# DeskAssistant_v19_v5.net
KiCad netlist of a schematic drawn in EAGLE
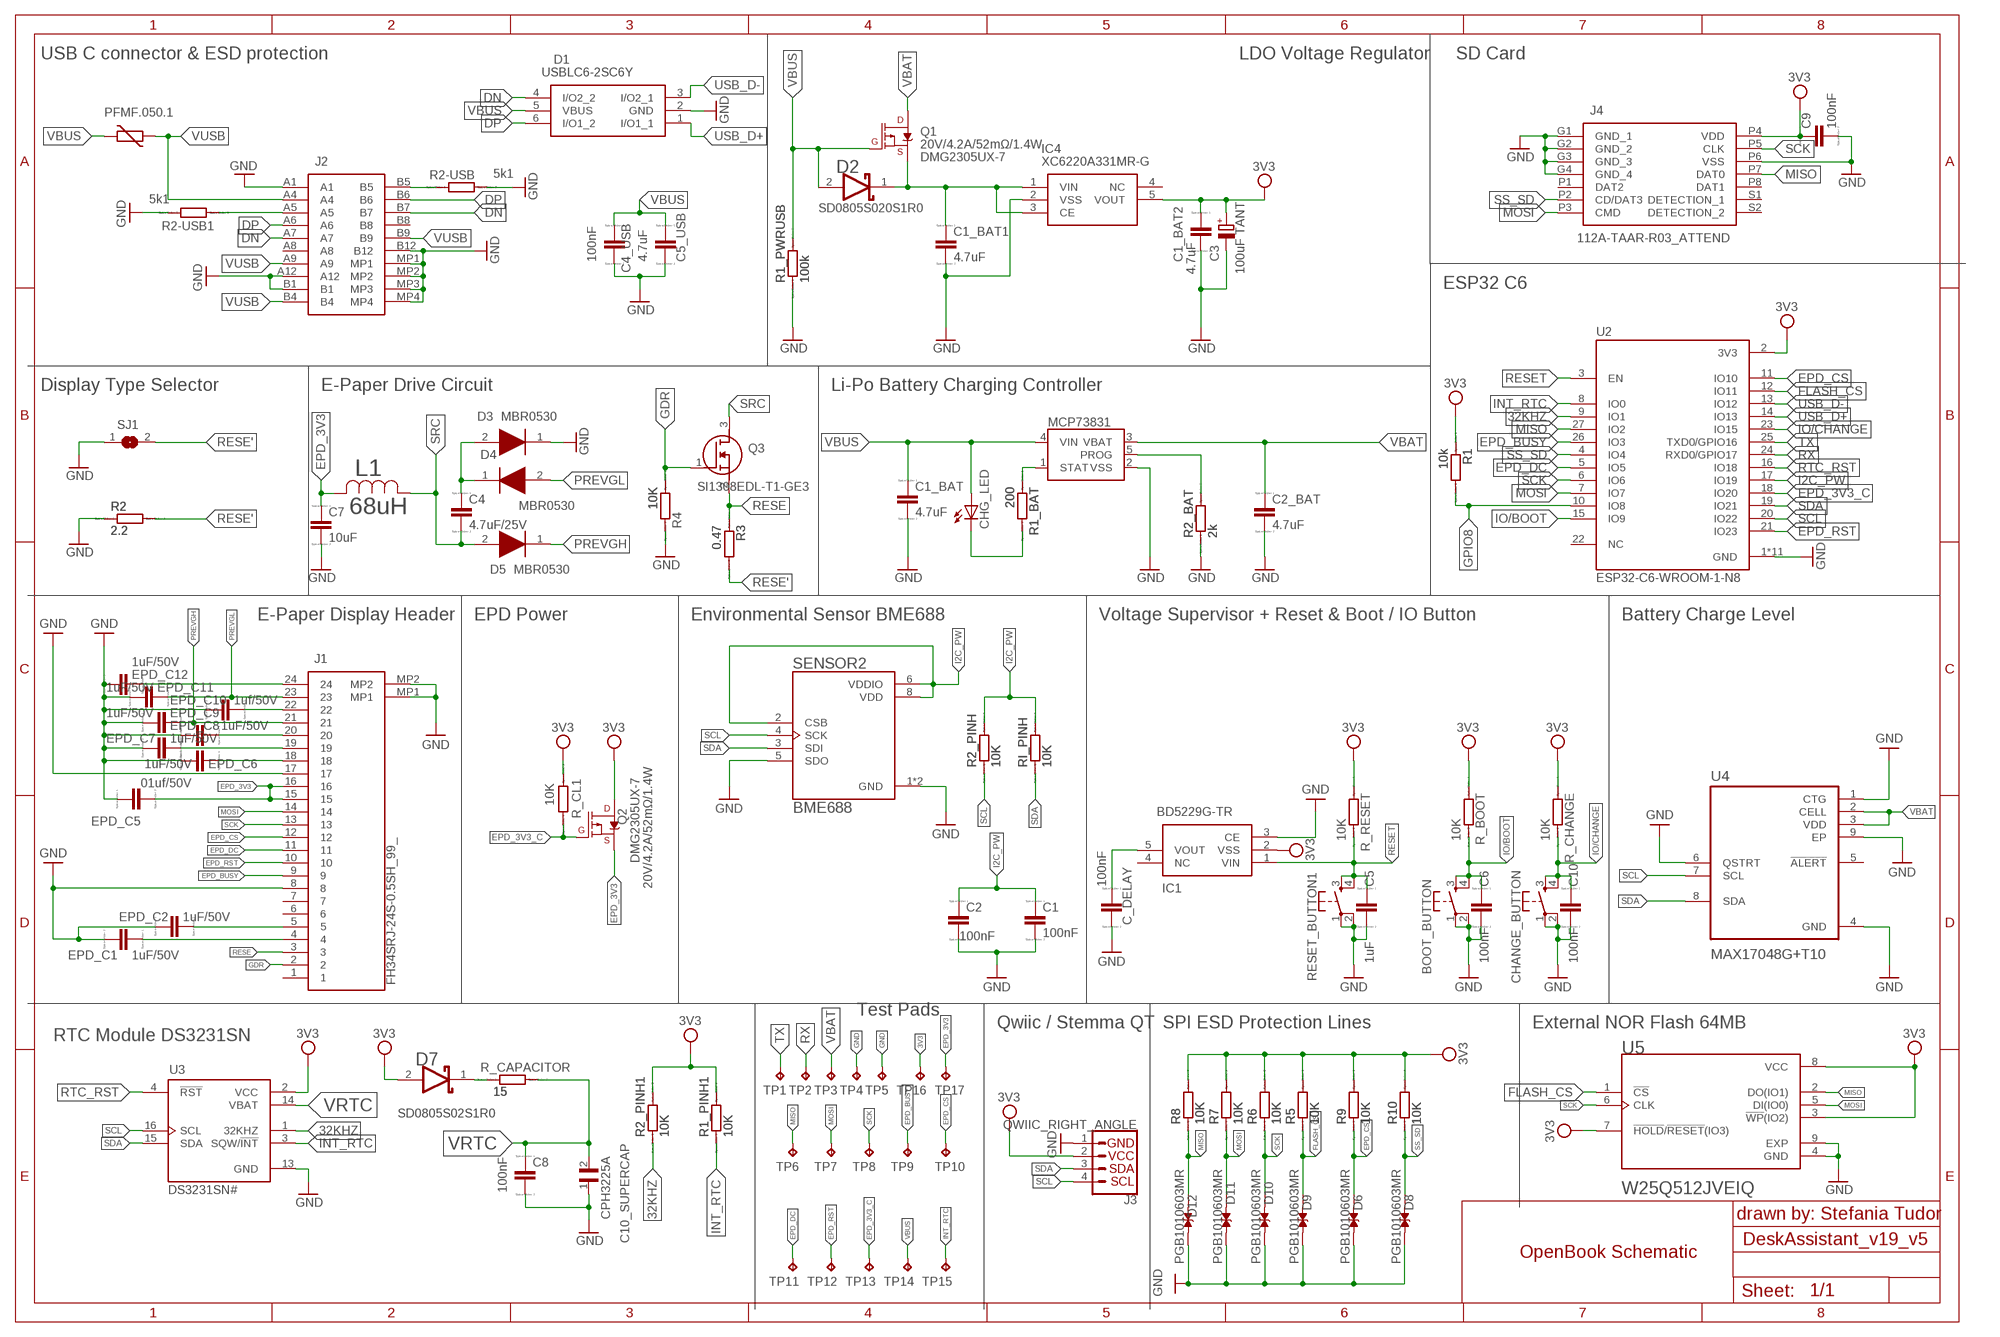
[diagram p0: schematic, sheet 1]

(export (version "E")
  (design (tool "Eeschema 10.0.6"))
  (components
    (comp (ref "BOOT_BUTTON")
      (value "BUTTON_CUSYOMV1")
      (footprint "eagle-import:MYBUTTON")
      (libsource (lib "eagle-import") (part "BUTTON_CUSYOMV1"))
    )
    (comp (ref "C1")
      (value "100nF")
      (footprint "eagle-import:ESP32_WROVER_EAGLE-LTSPICE_C0402")
      (libsource (lib "eagle-import") (part "DeskAssistant v19 v1_vf.Y-jMunlnQOyiXnQzDnYMGA_ESP32_WROVER_EAGLE-LTSPICE_CC0402"))
    )
    (comp (ref "C1_BAT")
      (value "4.7uF")
      (footprint "eagle-import:ESP32_WROVER_EAGLE-LTSPICE_C0402")
      (libsource (lib "eagle-import") (part "ESP32_WROVER_EAGLE-LTSPICE_CC0402"))
    )
    (comp (ref "C1_BAT1")
      (value "4.7uF")
      (footprint "eagle-import:EAGLE-LTSPICE_C0402")
      (libsource (lib "eagle-import") (part "EAGLE-LTSPICE_CC0402"))
    )
    (comp (ref "C1_BAT2")
      (value "4.7uF")
      (footprint "eagle-import:ESP32_WROVER_EAGLE-LTSPICE_C0402")
      (libsource (lib "eagle-import") (part "ESP32_WROVER_EAGLE-LTSPICE_CC0402"))
    )
    (comp (ref "C2")
      (value "100nF")
      (footprint "eagle-import:ESP32_WROVER_EAGLE-LTSPICE_C0402")
      (libsource (lib "eagle-import") (part "DeskAssistant v19 v1_vf.Y-jMunlnQOyiXnQzDnYMGA_ESP32_WROVER_EAGLE-LTSPICE_CC0402"))
    )
    (comp (ref "C2_BAT")
      (value "4.7uF")
      (footprint "eagle-import:ESP32_WROVER_EAGLE-LTSPICE_C0402")
      (libsource (lib "eagle-import") (part "ESP32_WROVER_EAGLE-LTSPICE_CC0402"))
    )
    (comp (ref "C3")
      (value "100uF TANT")
      (footprint "eagle-import:RCL_CT3528")
      (libsource (lib "eagle-import") (part "RCL_CPOL-EUCT3528"))
    )
    (comp (ref "C4")
      (value "4.7uF/25V")
      (footprint "eagle-import:ESP32_WROVER_EAGLE-LTSPICE_C0402")
      (libsource (lib "eagle-import") (part "ESP32_WROVER_EAGLE-LTSPICE_CC0402"))
    )
    (comp (ref "C4_USB")
      (value "100nF")
      (footprint "eagle-import:EAGLE-LTSPICE_C0402")
      (libsource (lib "eagle-import") (part "EAGLE-LTSPICE_CC0402"))
    )
    (comp (ref "C5")
      (value "1uF")
      (footprint "eagle-import:ESP32_WROVER_EAGLE-LTSPICE_C0402")
      (libsource (lib "eagle-import") (part "DeskAssistant v19 v1_vf.Y-jMunlnQOyiXnQzDnYMGA_ESP32_WROVER_EAGLE-LTSPICE_CC0402"))
    )
    (comp (ref "C5_USB")
      (value "4.7uF")
      (footprint "eagle-import:EAGLE-LTSPICE_C0402")
      (libsource (lib "eagle-import") (part "EAGLE-LTSPICE_CC0402"))
    )
    (comp (ref "C6")
      (value "100nF")
      (footprint "eagle-import:ESP32_WROVER_EAGLE-LTSPICE_C0402")
      (libsource (lib "eagle-import") (part "DeskAssistant v19 v1_vf.Y-jMunlnQOyiXnQzDnYMGA_ESP32_WROVER_EAGLE-LTSPICE_CC0402"))
    )
    (comp (ref "C7")
      (value "10uF")
      (footprint "eagle-import:ESP32_WROVER_EAGLE-LTSPICE_C0402")
      (libsource (lib "eagle-import") (part "ESP32_WROVER_EAGLE-LTSPICE_CC0402"))
    )
    (comp (ref "C8")
      (value "100nF")
      (footprint "eagle-import:ESP32_WROVER_EAGLE-LTSPICE_C0402")
      (libsource (lib "eagle-import") (part "ESP32_WROVER_EAGLE-LTSPICE_CC0402"))
    )
    (comp (ref "C9")
      (value "100nF")
      (footprint "eagle-import:EAGLE-LTSPICE_C0402")
      (libsource (lib "eagle-import") (part "EAGLE-LTSPICE_CC0402"))
    )
    (comp (ref "C10")
      (value "100nF")
      (footprint "eagle-import:ESP32_WROVER_EAGLE-LTSPICE_C0402")
      (libsource (lib "eagle-import") (part "DeskAssistant v19 v1_vf.Y-jMunlnQOyiXnQzDnYMGA_ESP32_WROVER_EAGLE-LTSPICE_CC0402"))
    )
    (comp (ref "C10_SUPERCAP")
      (value "CPH3225A")
      (footprint "eagle-import:CAPCP3225X100N")
      (fields (field (name "MF") "Seiko Instruments"))
      (libsource (lib "eagle-import") (part "CPH3225A"))
    )
    (comp (ref "CHANGE_BUTTON")
      (value "BUTTON_CUSYOMV1")
      (footprint "eagle-import:MYBUTTON")
      (libsource (lib "eagle-import") (part "BUTTON_CUSYOMV1"))
    )
    (comp (ref "CHG_LED")
      (value "ADAFRUIT_LEDCHIP-LED0603")
      (footprint "eagle-import:ADAFRUIT_CHIP-LED0603")
      (libsource (lib "eagle-import") (part "ADAFRUIT_LEDCHIP-LED0603"))
    )
    (comp (ref "C_DELAY")
      (value "100nF")
      (footprint "eagle-import:ESP32_WROVER_EAGLE-LTSPICE_C0402")
      (libsource (lib "eagle-import") (part "DeskAssistant v19 v1_vf.Y-jMunlnQOyiXnQzDnYMGA_ESP32_WROVER_EAGLE-LTSPICE_CC0402"))
    )
    (comp (ref "D1")
      (value "USBLC6-2SC6Y")
      (footprint "eagle-import:SOT95P280X145-6N")
      (fields (field (name "MF") "STMicroelectronics"))
      (libsource (lib "eagle-import") (part "USBLC6-2SC6Y"))
    )
    (comp (ref "D2")
      (value "ESP32_WROVER_AVX---SD0805S020S1R0_AVX_SD0805S020S1R0_0_0AVX_SD0805S020S1R0_0_0")
      (footprint "eagle-import:ESP32_WROVER_AVX---SD0805S020S1R0_AVX_SD0805S020S1R0_0")
      (fields
        (field (name "DIGIKEY_PART_NUMBER") "478-7800-1-ND")
        (field (name "MF") "AVX")
        (field (name "MOUSER_PART_NUMBER") "581-SD0805S020S1R0")
      )
      (libsource (lib "eagle-import") (part "ESP32_WROVER_AVX---SD0805S020S1R0_AVX_SD0805S020S1R0_0_0AVX_SD0805S020S1R0_0_0"))
    )
    (comp (ref "D3")
      (value "MBR0530")
      (footprint "eagle-import:SOD3716X135N")
      (fields (field (name "MF") "ON Semiconductor"))
      (libsource (lib "eagle-import") (part "MBR0530"))
    )
    (comp (ref "D4")
      (value "MBR0530")
      (footprint "eagle-import:SOD3716X135N")
      (fields (field (name "MF") "ON Semiconductor"))
      (libsource (lib "eagle-import") (part "MBR0530"))
    )
    (comp (ref "D5")
      (value "MBR0530")
      (footprint "eagle-import:SOD3716X135N")
      (fields (field (name "MF") "ON Semiconductor"))
      (libsource (lib "eagle-import") (part "MBR0530"))
    )
    (comp (ref "D6")
      (value "PGB1010603MR")
      (footprint "eagle-import:DIOC1608X36N")
      (fields (field (name "MF") "Littelfuse Inc."))
      (libsource (lib "eagle-import") (part "PGB1010603MR"))
    )
    (comp (ref "D7")
      (value "ESP32_WROVER_AVX---SD0805S020S1R0_AVX_SD0805S020S1R0_0_0AVX_SD0805S020S1R0_0_0")
      (footprint "eagle-import:ESP32_WROVER_AVX---SD0805S020S1R0_AVX_SD0805S020S1R0_0")
      (fields
        (field (name "DIGIKEY_PART_NUMBER") "478-7800-1-ND")
        (field (name "MF") "AVX")
        (field (name "MOUSER_PART_NUMBER") "581-SD0805S020S1R0")
      )
      (libsource (lib "eagle-import") (part "ESP32_WROVER_AVX---SD0805S020S1R0_AVX_SD0805S020S1R0_0_0AVX_SD0805S020S1R0_0_0"))
    )
    (comp (ref "D8")
      (value "PGB1010603MR")
      (footprint "eagle-import:DIOC1608X36N")
      (fields (field (name "MF") "Littelfuse Inc."))
      (libsource (lib "eagle-import") (part "PGB1010603MR"))
    )
    (comp (ref "D9")
      (value "PGB1010603MR")
      (footprint "eagle-import:DIOC1608X36N")
      (fields (field (name "MF") "Littelfuse Inc."))
      (libsource (lib "eagle-import") (part "PGB1010603MR"))
    )
    (comp (ref "D10")
      (value "PGB1010603MR")
      (footprint "eagle-import:DIOC1608X36N")
      (fields (field (name "MF") "Littelfuse Inc."))
      (libsource (lib "eagle-import") (part "PGB1010603MR"))
    )
    (comp (ref "D11")
      (value "PGB1010603MR")
      (footprint "eagle-import:DIOC1608X36N")
      (fields (field (name "MF") "Littelfuse Inc."))
      (libsource (lib "eagle-import") (part "PGB1010603MR"))
    )
    (comp (ref "D12")
      (value "PGB1010603MR")
      (footprint "eagle-import:DIOC1608X36N")
      (fields (field (name "MF") "Littelfuse Inc."))
      (libsource (lib "eagle-import") (part "PGB1010603MR"))
    )
    (comp (ref "EPD_C1")
      (value "1uF/50V")
      (footprint "eagle-import:ESP32_WROVER_EAGLE-LTSPICE_C0402")
      (libsource (lib "eagle-import") (part "DeskAssistant v19 v1_vf.Y-jMunlnQOyiXnQzDnYMGA_ESP32_WROVER_EAGLE-LTSPICE_CC0402"))
    )
    (comp (ref "EPD_C2")
      (value "1uF/50V")
      (footprint "eagle-import:ESP32_WROVER_EAGLE-LTSPICE_C0402")
      (libsource (lib "eagle-import") (part "DeskAssistant v19 v1_vf.Y-jMunlnQOyiXnQzDnYMGA_ESP32_WROVER_EAGLE-LTSPICE_CC0402"))
    )
    (comp (ref "EPD_C5")
      (value "01uf/50V")
      (footprint "eagle-import:ESP32_WROVER_EAGLE-LTSPICE_C0402")
      (libsource (lib "eagle-import") (part "DeskAssistant v19 v1_vf.Y-jMunlnQOyiXnQzDnYMGA_ESP32_WROVER_EAGLE-LTSPICE_CC0402"))
    )
    (comp (ref "EPD_C6")
      (value "1uF/50V")
      (footprint "eagle-import:ESP32_WROVER_EAGLE-LTSPICE_C0402")
      (libsource (lib "eagle-import") (part "DeskAssistant v19 v1_vf.Y-jMunlnQOyiXnQzDnYMGA_ESP32_WROVER_EAGLE-LTSPICE_CC0402"))
    )
    (comp (ref "EPD_C7")
      (value "1uF/50V")
      (footprint "eagle-import:ESP32_WROVER_EAGLE-LTSPICE_C0402")
      (libsource (lib "eagle-import") (part "DeskAssistant v19 v1_vf.Y-jMunlnQOyiXnQzDnYMGA_ESP32_WROVER_EAGLE-LTSPICE_CC0402"))
    )
    (comp (ref "EPD_C8")
      (value "1uF/50V")
      (footprint "eagle-import:ESP32_WROVER_EAGLE-LTSPICE_C0402")
      (libsource (lib "eagle-import") (part "DeskAssistant v19 v1_vf.Y-jMunlnQOyiXnQzDnYMGA_ESP32_WROVER_EAGLE-LTSPICE_CC0402"))
    )
    (comp (ref "EPD_C9")
      (value "1uF/50V")
      (footprint "eagle-import:ESP32_WROVER_EAGLE-LTSPICE_C0402")
      (libsource (lib "eagle-import") (part "DeskAssistant v19 v1_vf.Y-jMunlnQOyiXnQzDnYMGA_ESP32_WROVER_EAGLE-LTSPICE_CC0402"))
    )
    (comp (ref "EPD_C10")
      (value "1uf/50V")
      (footprint "eagle-import:ESP32_WROVER_EAGLE-LTSPICE_C0402")
      (libsource (lib "eagle-import") (part "DeskAssistant v19 v1_vf.Y-jMunlnQOyiXnQzDnYMGA_ESP32_WROVER_EAGLE-LTSPICE_CC0402"))
    )
    (comp (ref "EPD_C11")
      (value "1uF/50V")
      (footprint "eagle-import:ESP32_WROVER_EAGLE-LTSPICE_C0402")
      (libsource (lib "eagle-import") (part "DeskAssistant v19 v1_vf.Y-jMunlnQOyiXnQzDnYMGA_ESP32_WROVER_EAGLE-LTSPICE_CC0402"))
    )
    (comp (ref "EPD_C12")
      (value "1uF/50V")
      (footprint "eagle-import:ESP32_WROVER_EAGLE-LTSPICE_C0402")
      (libsource (lib "eagle-import") (part "DeskAssistant v19 v1_vf.Y-jMunlnQOyiXnQzDnYMGA_ESP32_WROVER_EAGLE-LTSPICE_CC0402"))
    )
    (comp (ref "IC1")
      (value "BD5229G-TR")
      (footprint "eagle-import:SOT95P280X120-5N")
      (fields
        (field (name "MANUFACTURER_PART_NUMBER") "XC6220A331MR-G")
        (field (name "MOUSER_PART_NUMBER") "865-XC6220A331MR-G")
      )
      (libsource (lib "eagle-import") (part "DeskAssistant v19 v1_vf.Y-jMunlnQOyiXnQzDnYMGA_XC6220A331MR-G"))
    )
    (comp (ref "IC4")
      (value "XC6220A331MR-G")
      (footprint "eagle-import:SOT95P280X120-5N")
      (fields (field (name "MOUSER_PART_NUMBER") "865-XC6220A331MR-G"))
      (libsource (lib "eagle-import") (part "XC6220A331MR-G"))
    )
    (comp (ref "J1")
      (value "FH34SRJ-24S-0.5SH_99_")
      (footprint "eagle-import:FH34SRJ24S05SH99")
      (fields
        (field (name "MANUFACTURER_PART_NUMBER") "FH34SRJ-24S-0.5SH(99)")
        (field (name "MOUSER_PART_NUMBER") "798-FH34SRJ24S05SH99")
      )
      (libsource (lib "eagle-import") (part "FH34SRJ-24S-0.5SH_99_"))
    )
    (comp (ref "J2")
      (value "SAMACSYS_PARTS_USB4110-GF-A")
      (footprint "eagle-import:SAMACSYS_PARTS_USB4110GFA")
      (fields
        (field (name "MANUFACTURER_PART_NUMBER") "USB4110-GF-A")
        (field (name "MOUSER_PART_NUMBER") "640-USB4110-GF-A")
      )
      (libsource (lib "eagle-import") (part "SAMACSYS_PARTS_USB4110-GF-A"))
    )
    (comp (ref "J3")
      (value "QWIIC_RIGHT_ANGLE")
      (footprint "eagle-import:JST04_1MM_RA")
      (libsource (lib "eagle-import") (part "QWIIC_CONNECTORJS-1MM"))
    )
    (comp (ref "J4")
      (value "112A-TAAR-R03_ATTEND")
      (footprint "eagle-import:112ATAARR03ATTEND")
      (fields (field (name "MANUFACTURER_PART_NUMBER") "112A-TAAR-R03 ATTEND"))
      (libsource (lib "eagle-import") (part "112A-TAAR-R03_ATTEND"))
    )
    (comp (ref "L1")
      (value "68uH")
      (footprint "eagle-import:IND_4828-WE-TPC_WRE")
      (fields
        (field (name "MANUFACTURER_PART_NUMBER") "744043680")
        (field (name "COPYRIGHT") "Copyright (C) 2024 Ultra Librarian. All rights reserved.")
      )
      (libsource (lib "eagle-import") (part "744043680IND_4828-WE-TPC_WRE"))
    )
    (comp (ref "MCP73831")
      (value "ESP32_WROVER_SPARKFUN-IC-POWER_MCP73831")
      (footprint "eagle-import:ESP32_WROVER_SPARKFUN-IC-POWER_SOT23-5")
      (libsource (lib "eagle-import") (part "ESP32_WROVER_SPARKFUN-IC-POWER_MCP73831"))
    )
    (comp (ref "PFMF.050.1")
      (value "ESP32C6_VARISTORCN1812")
      (footprint "eagle-import:ESP32C6_VARISTOR_CT_CN1812")
      (libsource (lib "eagle-import") (part "ESP32C6_VARISTORCN1812"))
    )
    (comp (ref "Q1")
      (value "20V/4.2A/52mΩ/1.4W")
      (footprint "eagle-import:ESP32_WROVER_SPARKFUN-DISCRETESEMI_SOT23-3")
      (libsource (lib "eagle-import") (part "ESP32_WROVER_SPARKFUN-DISCRETESEMI_MOSFET_PCH-DMG2305UX-7"))
    )
    (comp (ref "Q2")
      (value "20V/4.2A/52mΩ/1.4W")
      (footprint "eagle-import:ESP32_WROVER_SPARKFUN-DISCRETESEMI_SOT23-3")
      (libsource (lib "eagle-import") (part "DeskAssistant v19 v1_vf.Y-jMunlnQOyiXnQzDnYMGA_ESP32_WROVER_SPARKFUN-DISCRETESEMI_MOSFET_PCH-DMG2305UX-7"))
    )
    (comp (ref "Q3")
      (value "SI1308EDL-T1-GE3")
      (footprint "eagle-import:SOT65P210X110-3N")
      (fields (field (name "MF") "Vishay Siliconix"))
      (libsource (lib "eagle-import") (part "SI1308EDL-T1-GE3"))
    )
    (comp (ref "R1")
      (value "10k")
      (footprint "eagle-import:ESP32_WROVER_EAGLE-LTSPICE_R0402")
      (libsource (lib "eagle-import") (part "ESP32_WROVER_EAGLE-LTSPICE_RR0402"))
    )
    (comp (ref "R1_BAT")
      (value "200")
      (footprint "eagle-import:ESP32_WROVER_EAGLE-LTSPICE_R0402")
      (libsource (lib "eagle-import") (part "ESP32_WROVER_EAGLE-LTSPICE_RR0402"))
    )
    (comp (ref "R1_PINH1")
      (value "10K")
      (footprint "eagle-import:ESP32_WROVER_EAGLE-LTSPICE_R0402")
      (libsource (lib "eagle-import") (part "ESP32_WROVER_EAGLE-LTSPICE_RR0402"))
    )
    (comp (ref "R1_PWRUSB")
      (value "100k")
      (footprint "eagle-import:ESP32_WROVER_EAGLE-LTSPICE_R0402")
      (libsource (lib "eagle-import") (part "ESP32_WROVER_EAGLE-LTSPICE_RR0402"))
    )
    (comp (ref "R2")
      (value "2.2")
      (footprint "eagle-import:ESP32_WROVER_EAGLE-LTSPICE_R0402")
      (libsource (lib "eagle-import") (part "ESP32_WROVER_EAGLE-LTSPICE_RR0402"))
    )
    (comp (ref "R2-USB")
      (value "5k1")
      (footprint "eagle-import:ESP32_WROVER_EAGLE-LTSPICE_R0402")
      (libsource (lib "eagle-import") (part "ESP32_WROVER_EAGLE-LTSPICE_RR0402"))
    )
    (comp (ref "R2-USB1")
      (value "5k1")
      (footprint "eagle-import:ESP32_WROVER_EAGLE-LTSPICE_R0402")
      (libsource (lib "eagle-import") (part "ESP32_WROVER_EAGLE-LTSPICE_RR0402"))
    )
    (comp (ref "R2_BAT")
      (value "2k")
      (footprint "eagle-import:ESP32_WROVER_EAGLE-LTSPICE_R0402")
      (libsource (lib "eagle-import") (part "ESP32_WROVER_EAGLE-LTSPICE_RR0402"))
    )
    (comp (ref "R2_PINH")
      (value "10K")
      (footprint "eagle-import:ESP32_WROVER_EAGLE-LTSPICE_R0402")
      (libsource (lib "eagle-import") (part "DeskAssistant v19 v1_vf.Y-jMunlnQOyiXnQzDnYMGA_ESP32_WROVER_EAGLE-LTSPICE_RR0402"))
    )
    (comp (ref "R2_PINH1")
      (value "10K")
      (footprint "eagle-import:ESP32_WROVER_EAGLE-LTSPICE_R0402")
      (libsource (lib "eagle-import") (part "ESP32_WROVER_EAGLE-LTSPICE_RR0402"))
    )
    (comp (ref "R3")
      (value "0.47")
      (footprint "eagle-import:ESP32_WROVER_EAGLE-LTSPICE_R0402")
      (libsource (lib "eagle-import") (part "ESP32_WROVER_EAGLE-LTSPICE_RR0402"))
    )
    (comp (ref "R4")
      (value "10K")
      (footprint "eagle-import:ESP32_WROVER_EAGLE-LTSPICE_R0402")
      (libsource (lib "eagle-import") (part "ESP32_WROVER_EAGLE-LTSPICE_RR0402"))
    )
    (comp (ref "R5")
      (value "10K")
      (footprint "eagle-import:ESP32_WROVER_EAGLE-LTSPICE_R0402")
      (libsource (lib "eagle-import") (part "ESP32_WROVER_EAGLE-LTSPICE_RR0402"))
    )
    (comp (ref "R6")
      (value "10K")
      (footprint "eagle-import:ESP32_WROVER_EAGLE-LTSPICE_R0402")
      (libsource (lib "eagle-import") (part "ESP32_WROVER_EAGLE-LTSPICE_RR0402"))
    )
    (comp (ref "R7")
      (value "10K")
      (footprint "eagle-import:ESP32_WROVER_EAGLE-LTSPICE_R0402")
      (libsource (lib "eagle-import") (part "ESP32_WROVER_EAGLE-LTSPICE_RR0402"))
    )
    (comp (ref "R8")
      (value "10K")
      (footprint "eagle-import:ESP32_WROVER_EAGLE-LTSPICE_R0402")
      (libsource (lib "eagle-import") (part "ESP32_WROVER_EAGLE-LTSPICE_RR0402"))
    )
    (comp (ref "R9")
      (value "10K")
      (footprint "eagle-import:ESP32_WROVER_EAGLE-LTSPICE_R0402")
      (libsource (lib "eagle-import") (part "ESP32_WROVER_EAGLE-LTSPICE_RR0402"))
    )
    (comp (ref "R10")
      (value "10K")
      (footprint "eagle-import:ESP32_WROVER_EAGLE-LTSPICE_R0402")
      (libsource (lib "eagle-import") (part "ESP32_WROVER_EAGLE-LTSPICE_RR0402"))
    )
    (comp (ref "RESET_BUTTON1")
      (value "BUTTON_CUSYOMV1")
      (footprint "eagle-import:MYBUTTON")
      (libsource (lib "eagle-import") (part "BUTTON_CUSYOMV1"))
    )
    (comp (ref "RI_PINH")
      (value "10K")
      (footprint "eagle-import:ESP32_WROVER_EAGLE-LTSPICE_R0402")
      (libsource (lib "eagle-import") (part "DeskAssistant v19 v1_vf.Y-jMunlnQOyiXnQzDnYMGA_ESP32_WROVER_EAGLE-LTSPICE_RR0402"))
    )
    (comp (ref "R_BOOT")
      (value "10K")
      (footprint "eagle-import:ESP32_WROVER_EAGLE-LTSPICE_R0402")
      (libsource (lib "eagle-import") (part "DeskAssistant v19 v1_vf.Y-jMunlnQOyiXnQzDnYMGA_ESP32_WROVER_EAGLE-LTSPICE_RR0402"))
    )
    (comp (ref "R_CAPACITOR")
      (value "15")
      (footprint "eagle-import:ESP32_WROVER_EAGLE-LTSPICE_R0402")
      (libsource (lib "eagle-import") (part "ESP32_WROVER_EAGLE-LTSPICE_RR0402"))
    )
    (comp (ref "R_CHANGE")
      (value "10K")
      (footprint "eagle-import:ESP32_WROVER_EAGLE-LTSPICE_R0402")
      (libsource (lib "eagle-import") (part "DeskAssistant v19 v1_vf.Y-jMunlnQOyiXnQzDnYMGA_ESP32_WROVER_EAGLE-LTSPICE_RR0402"))
    )
    (comp (ref "R_CL1")
      (value "10K")
      (footprint "eagle-import:ESP32_WROVER_EAGLE-LTSPICE_R0402")
      (libsource (lib "eagle-import") (part "DeskAssistant v19 v1_vf.Y-jMunlnQOyiXnQzDnYMGA_ESP32_WROVER_EAGLE-LTSPICE_RR0402"))
    )
    (comp (ref "R_RESET")
      (value "10K")
      (footprint "eagle-import:ESP32_WROVER_EAGLE-LTSPICE_R0402")
      (libsource (lib "eagle-import") (part "DeskAssistant v19 v1_vf.Y-jMunlnQOyiXnQzDnYMGA_ESP32_WROVER_EAGLE-LTSPICE_RR0402"))
    )
    (comp (ref "SENSOR2")
      (value "BME688")
      (footprint "eagle-import:ESP32_WROVER_BME680_PSON80P300X300X100-8N")
      (fields (field (name "MF") "Bosch Sensortec") (field (name "MP") "BME680"))
      (libsource (lib "eagle-import") (part "ESP32_WROVER_BME680_BME680"))
    )
    (comp (ref "SJ1") (value "SJ") (footprint "eagle-import:SJ") (libsource (lib "eagle-import") (part "SJ")))
    (comp (ref "TP1")
      (value "TPTP20R")
      (footprint "eagle-import:TP20R")
      (libsource (lib "eagle-import") (part "TPTP20R"))
    )
    (comp (ref "TP2")
      (value "TPTP20R")
      (footprint "eagle-import:TP20R")
      (libsource (lib "eagle-import") (part "TPTP20R"))
    )
    (comp (ref "TP3")
      (value "TPTP20R")
      (footprint "eagle-import:TP20R")
      (libsource (lib "eagle-import") (part "TPTP20R"))
    )
    (comp (ref "TP4")
      (value "TPTP20R")
      (footprint "eagle-import:TP20R")
      (libsource (lib "eagle-import") (part "TPTP20R"))
    )
    (comp (ref "TP5")
      (value "TPTP20R")
      (footprint "eagle-import:TP20R")
      (libsource (lib "eagle-import") (part "TPTP20R"))
    )
    (comp (ref "TP6")
      (value "TPTP20R")
      (footprint "eagle-import:TP20R")
      (libsource (lib "eagle-import") (part "TPTP20R"))
    )
    (comp (ref "TP7")
      (value "TPTP20R")
      (footprint "eagle-import:TP20R")
      (libsource (lib "eagle-import") (part "TPTP20R"))
    )
    (comp (ref "TP8")
      (value "TPTP20R")
      (footprint "eagle-import:TP20R")
      (libsource (lib "eagle-import") (part "TPTP20R"))
    )
    (comp (ref "TP9")
      (value "TPTP20R")
      (footprint "eagle-import:TP20R")
      (libsource (lib "eagle-import") (part "TPTP20R"))
    )
    (comp (ref "TP10")
      (value "TPTP20R")
      (footprint "eagle-import:TP20R")
      (libsource (lib "eagle-import") (part "TPTP20R"))
    )
    (comp (ref "TP11")
      (value "TPTP20R")
      (footprint "eagle-import:TP20R")
      (libsource (lib "eagle-import") (part "TPTP20R"))
    )
    (comp (ref "TP12")
      (value "TPTP20R")
      (footprint "eagle-import:TP20R")
      (libsource (lib "eagle-import") (part "TPTP20R"))
    )
    (comp (ref "TP13")
      (value "TPTP20R")
      (footprint "eagle-import:TP20R")
      (libsource (lib "eagle-import") (part "TPTP20R"))
    )
    (comp (ref "TP14")
      (value "TPTP20R")
      (footprint "eagle-import:TP20R")
      (libsource (lib "eagle-import") (part "TPTP20R"))
    )
    (comp (ref "TP15")
      (value "TPTP20R")
      (footprint "eagle-import:TP20R")
      (libsource (lib "eagle-import") (part "TPTP20R"))
    )
    (comp (ref "TP16")
      (value "TPTP20R")
      (footprint "eagle-import:TP20R")
      (libsource (lib "eagle-import") (part "TPTP20R"))
    )
    (comp (ref "TP17")
      (value "TPTP20R")
      (footprint "eagle-import:TP20R")
      (libsource (lib "eagle-import") (part "TPTP20R"))
    )
    (comp (ref "U2")
      (value "ESP32-C6-WROOM-1-N8")
      (footprint "eagle-import:XCVR_ESP32-C6-WROOM-1-N8")
      (fields (field (name "MF") "Espressif Systems"))
      (libsource (lib "eagle-import") (part "ESP32-C6-WROOM-1-N8"))
    )
    (comp (ref "U3")
      (value "DS3231SN#")
      (footprint "eagle-import:SOIC127P1032X265-16N")
      (fields (field (name "MF") "Analog Devices"))
      (libsource (lib "eagle-import") (part "DS3231SN#"))
    )
    (comp (ref "U4")
      (value "MAX17048G+T10")
      (footprint "eagle-import:SON50P200X200X80-9N")
      (fields (field (name "MF") "Analog Devices"))
      (libsource (lib "eagle-import") (part "MAX17048G+T10"))
    )
    (comp (ref "U5")
      (value "W25Q512JVEIQ")
      (footprint "eagle-import:SON127P600X800X80-9N")
      (fields (field (name "MF") "Winbond Electronics"))
      (libsource (lib "eagle-import") (part "W25Q512JVEIQ"))
    )
  )
  (nets
    (net (code "1") (name "3V3") (class "Default")
      (node (ref "C1_BAT2") (pin "1") (pinfunction "1_1") (pintype "passive"))
      (node (ref "C3") (pin "+") (pinfunction "+_+") (pintype "passive"))
      (node (ref "C9") (pin "1") (pinfunction "1_1") (pintype "passive"))
      (node (ref "D7") (pin "2") (pinfunction "ANODE_2") (pintype "bidirectional"))
      (node (ref "IC1") (pin "2") (pinfunction "VSS_2") (pintype "bidirectional"))
      (node (ref "IC4") (pin "5") (pinfunction "VOUT_5") (pintype "bidirectional"))
      (node (ref "J3") (pin "2") (pinfunction "2_2") (pintype "power_in"))
      (node (ref "J4") (pin "P4") (pinfunction "VDD_P4") (pintype "bidirectional"))
      (node (ref "Q2") (pin "3") (pinfunction "D_3") (pintype "bidirectional"))
      (node (ref "R1") (pin "1") (pinfunction "1_1") (pintype "passive"))
      (node (ref "R10") (pin "2") (pinfunction "2_2") (pintype "passive"))
      (node (ref "R1_PINH1") (pin "2") (pinfunction "2_2") (pintype "passive"))
      (node (ref "R2_PINH1") (pin "2") (pinfunction "2_2") (pintype "passive"))
      (node (ref "R5") (pin "2") (pinfunction "2_2") (pintype "passive"))
      (node (ref "R6") (pin "2") (pinfunction "2_2") (pintype "passive"))
      (node (ref "R7") (pin "2") (pinfunction "2_2") (pintype "passive"))
      (node (ref "R8") (pin "2") (pinfunction "2_2") (pintype "passive"))
      (node (ref "R9") (pin "2") (pinfunction "2_2") (pintype "passive"))
      (node (ref "R_BOOT") (pin "1") (pinfunction "1_1") (pintype "passive"))
      (node (ref "R_CHANGE") (pin "1") (pinfunction "1_1") (pintype "passive"))
      (node (ref "R_CL1") (pin "2") (pinfunction "2_2") (pintype "passive"))
      (node (ref "R_RESET") (pin "1") (pinfunction "1_1") (pintype "passive"))
      (node (ref "TP16") (pin "TP") (pinfunction "TP_TP") (pintype "input"))
      (node (ref "U2") (pin "2") (pinfunction "3V3_2") (pintype "power_in"))
      (node (ref "U3") (pin "2") (pinfunction "VCC_2") (pintype "power_in"))
      (node (ref "U5") (pin "3") (pinfunction "~{WP}(IO2)_3") (pintype "bidirectional"))
      (node (ref "U5") (pin "7") (pinfunction "~{HOLD}/~{RESET}(IO3)_7") (pintype "bidirectional"))
      (node (ref "U5") (pin "8") (pinfunction "VCC_8") (pintype "power_in"))
    )
    (net (code "2") (name "32KHZ") (class "Default")
      (node (ref "R2_PINH1") (pin "1") (pinfunction "1_1") (pintype "passive"))
      (node (ref "U2") (pin "9") (pinfunction "IO1_9") (pintype "bidirectional"))
      (node (ref "U3") (pin "1") (pinfunction "32KHZ_1") (pintype "output"))
    )
    (net (code "3") (name "DN") (class "Default")
      (node (ref "J2") (pin "A7") (pinfunction "A7_A7") (pintype "bidirectional"))
    )
    (net (code "4") (name "DP") (class "Default")
      (node (ref "J2") (pin "A6") (pinfunction "A6_A6") (pintype "bidirectional"))
    )
    (net (code "5") (name "EPD_3V3") (class "Default")
      (node (ref "C7") (pin "1") (pinfunction "1_1") (pintype "passive"))
      (node (ref "EPD_C5") (pin "2") (pinfunction "2_2") (pintype "passive"))
      (node (ref "J1") (pin "15") (pinfunction "15_15") (pintype "bidirectional"))
      (node (ref "J1") (pin "16") (pinfunction "16_16") (pintype "bidirectional"))
      (node (ref "L1") (pin "2") (pinfunction "2_2") (pintype "passive"))
      (node (ref "Q2") (pin "2") (pinfunction "S_2") (pintype "bidirectional"))
      (node (ref "TP17") (pin "TP") (pinfunction "TP_TP") (pintype "input"))
    )
    (net (code "6") (name "EPD_3V3_C") (class "Default")
      (node (ref "Q2") (pin "1") (pinfunction "G_1") (pintype "bidirectional"))
      (node (ref "R_CL1") (pin "1") (pinfunction "1_1") (pintype "passive"))
      (node (ref "TP13") (pin "TP") (pinfunction "TP_TP") (pintype "input"))
      (node (ref "U2") (pin "18") (pinfunction "IO20_18") (pintype "bidirectional"))
    )
    (net (code "7") (name "EPD_BUSY") (class "Default")
      (node (ref "J1") (pin "9") (pinfunction "9_9") (pintype "bidirectional"))
      (node (ref "TP9") (pin "TP") (pinfunction "TP_TP") (pintype "input"))
      (node (ref "U2") (pin "26") (pinfunction "IO3_26") (pintype "bidirectional"))
    )
    (net (code "8") (name "EPD_CS") (class "Default")
      (node (ref "D6") (pin "1") (pinfunction "1_1") (pintype "passive"))
      (node (ref "J1") (pin "12") (pinfunction "12_12") (pintype "bidirectional"))
      (node (ref "R9") (pin "1") (pinfunction "1_1") (pintype "passive"))
      (node (ref "TP10") (pin "TP") (pinfunction "TP_TP") (pintype "input"))
      (node (ref "U2") (pin "11") (pinfunction "IO10_11") (pintype "bidirectional"))
    )
    (net (code "9") (name "EPD_DC") (class "Default")
      (node (ref "J1") (pin "11") (pinfunction "11_11") (pintype "bidirectional"))
      (node (ref "TP11") (pin "TP") (pinfunction "TP_TP") (pintype "input"))
      (node (ref "U2") (pin "5") (pinfunction "IO5_5") (pintype "bidirectional"))
    )
    (net (code "10") (name "EPD_RST") (class "Default")
      (node (ref "J1") (pin "10") (pinfunction "10_10") (pintype "bidirectional"))
      (node (ref "TP12") (pin "TP") (pinfunction "TP_TP") (pintype "input"))
      (node (ref "U2") (pin "21") (pinfunction "IO23_21") (pintype "bidirectional"))
    )
    (net (code "11") (name "FLASH_CS") (class "Default")
      (node (ref "D9") (pin "1") (pinfunction "1_1") (pintype "passive"))
      (node (ref "R5") (pin "1") (pinfunction "1_1") (pintype "passive"))
      (node (ref "U2") (pin "12") (pinfunction "IO11_12") (pintype "bidirectional"))
      (node (ref "U5") (pin "1") (pinfunction "~{CS}_1") (pintype "input"))
    )
    (net (code "12") (name "GDR") (class "Default")
      (node (ref "J1") (pin "2") (pinfunction "2_2") (pintype "bidirectional"))
      (node (ref "Q3") (pin "1") (pinfunction "G_1") (pintype "bidirectional"))
      (node (ref "R4") (pin "1") (pinfunction "1_1") (pintype "passive"))
    )
    (net (code "13") (name "GND") (class "Default")
      (node (ref "BOOT_BUTTON") (pin "1") (pinfunction "1_1") (pintype "passive"))
      (node (ref "BOOT_BUTTON") (pin "2") (pinfunction "2_2") (pintype "passive"))
      (node (ref "C1") (pin "2") (pinfunction "2_2") (pintype "passive"))
      (node (ref "C10") (pin "2") (pinfunction "2_2") (pintype "passive"))
      (node (ref "C10_SUPERCAP") (pin "1") (pinfunction "1_1") (pintype "passive"))
      (node (ref "C1_BAT") (pin "2") (pinfunction "2_2") (pintype "passive"))
      (node (ref "C1_BAT1") (pin "2") (pinfunction "2_2") (pintype "passive"))
      (node (ref "C1_BAT2") (pin "2") (pinfunction "2_2") (pintype "passive"))
      (node (ref "C2") (pin "2") (pinfunction "2_2") (pintype "passive"))
      (node (ref "C2_BAT") (pin "2") (pinfunction "2_2") (pintype "passive"))
      (node (ref "C3") (pin "-") (pinfunction "-_-") (pintype "passive"))
      (node (ref "C4_USB") (pin "2") (pinfunction "2_2") (pintype "passive"))
      (node (ref "C5") (pin "2") (pinfunction "2_2") (pintype "passive"))
      (node (ref "C5_USB") (pin "2") (pinfunction "2_2") (pintype "passive"))
      (node (ref "C6") (pin "2") (pinfunction "2_2") (pintype "passive"))
      (node (ref "C7") (pin "2") (pinfunction "2_2") (pintype "passive"))
      (node (ref "C8") (pin "2") (pinfunction "2_2") (pintype "passive"))
      (node (ref "C9") (pin "2") (pinfunction "2_2") (pintype "passive"))
      (node (ref "CHANGE_BUTTON") (pin "1") (pinfunction "1_1") (pintype "passive"))
      (node (ref "CHANGE_BUTTON") (pin "2") (pinfunction "2_2") (pintype "passive"))
      (node (ref "C_DELAY") (pin "2") (pinfunction "2_2") (pintype "passive"))
      (node (ref "D1") (pin "2") (pinfunction "GND_2") (pintype "bidirectional"))
      (node (ref "D10") (pin "2") (pinfunction "2_2") (pintype "passive"))
      (node (ref "D11") (pin "2") (pinfunction "2_2") (pintype "passive"))
      (node (ref "D12") (pin "2") (pinfunction "2_2") (pintype "passive"))
      (node (ref "D3") (pin "1") (pinfunction "K_1") (pintype "bidirectional"))
      (node (ref "D6") (pin "2") (pinfunction "2_2") (pintype "passive"))
      (node (ref "D8") (pin "2") (pinfunction "2_2") (pintype "passive"))
      (node (ref "D9") (pin "2") (pinfunction "2_2") (pintype "passive"))
      (node (ref "EPD_C1") (pin "2") (pinfunction "2_2") (pintype "passive"))
      (node (ref "EPD_C10") (pin "2") (pinfunction "2_2") (pintype "passive"))
      (node (ref "EPD_C11") (pin "2") (pinfunction "2_2") (pintype "passive"))
      (node (ref "EPD_C12") (pin "2") (pinfunction "2_2") (pintype "passive"))
      (node (ref "EPD_C2") (pin "2") (pinfunction "2_2") (pintype "passive"))
      (node (ref "EPD_C5") (pin "1") (pinfunction "1_1") (pintype "passive"))
      (node (ref "EPD_C6") (pin "2") (pinfunction "2_2") (pintype "passive"))
      (node (ref "EPD_C7") (pin "2") (pinfunction "2_2") (pintype "passive"))
      (node (ref "EPD_C8") (pin "2") (pinfunction "2_2") (pintype "passive"))
      (node (ref "EPD_C9") (pin "2") (pinfunction "2_2") (pintype "passive"))
      (node (ref "IC1") (pin "3") (pinfunction "CE_3") (pintype "bidirectional"))
      (node (ref "IC4") (pin "2") (pinfunction "VSS_2") (pintype "bidirectional"))
      (node (ref "J1") (pin "17") (pinfunction "17_17") (pintype "bidirectional"))
      (node (ref "J1") (pin "8") (pinfunction "8_8") (pintype "bidirectional"))
      (node (ref "J1") (pin "MP1") (pinfunction "MP1_MP1") (pintype "bidirectional"))
      (node (ref "J1") (pin "MP2") (pinfunction "MP2_MP2") (pintype "bidirectional"))
      (node (ref "J2") (pin "A1") (pinfunction "A1_A1") (pintype "bidirectional"))
      (node (ref "J2") (pin "A12") (pinfunction "A12_A12") (pintype "bidirectional"))
      (node (ref "J2") (pin "B1") (pinfunction "B1_B1") (pintype "bidirectional"))
      (node (ref "J2") (pin "B12") (pinfunction "B12_B12") (pintype "bidirectional"))
      (node (ref "J2") (pin "MP1") (pinfunction "MP1_MP1") (pintype "bidirectional"))
      (node (ref "J2") (pin "MP2") (pinfunction "MP2_MP2") (pintype "bidirectional"))
      (node (ref "J2") (pin "MP3") (pinfunction "MP3_MP3") (pintype "bidirectional"))
      (node (ref "J2") (pin "MP4") (pinfunction "MP4_MP4") (pintype "bidirectional"))
      (node (ref "J3") (pin "1") (pinfunction "1_1") (pintype "power_in"))
      (node (ref "J4") (pin "G1") (pinfunction "GND_1_G1") (pintype "bidirectional"))
      (node (ref "J4") (pin "G2") (pinfunction "GND_2_G2") (pintype "bidirectional"))
      (node (ref "J4") (pin "G3") (pinfunction "GND_3_G3") (pintype "bidirectional"))
      (node (ref "J4") (pin "G4") (pinfunction "GND_4_G4") (pintype "bidirectional"))
      (node (ref "J4") (pin "P6") (pinfunction "VSS_P6") (pintype "bidirectional"))
      (node (ref "MCP73831") (pin "2") (pinfunction "VSS_2") (pintype "power_in"))
      (node (ref "R1_PWRUSB") (pin "1") (pinfunction "1_1") (pintype "passive"))
      (node (ref "R2") (pin "1") (pinfunction "1_1") (pintype "passive"))
      (node (ref "R2-USB") (pin "2") (pinfunction "2_2") (pintype "passive"))
      (node (ref "R2-USB1") (pin "1") (pinfunction "1_1") (pintype "passive"))
      (node (ref "R2_BAT") (pin "1") (pinfunction "1_1") (pintype "passive"))
      (node (ref "R4") (pin "2") (pinfunction "2_2") (pintype "passive"))
      (node (ref "RESET_BUTTON1") (pin "1") (pinfunction "1_1") (pintype "passive"))
      (node (ref "RESET_BUTTON1") (pin "2") (pinfunction "2_2") (pintype "passive"))
      (node (ref "SENSOR2") (pin "1") (pinfunction "GND_1") (pintype "power_in"))
      (node (ref "SENSOR2") (pin "5") (pinfunction "SDO_5") (pintype "bidirectional"))
      (node (ref "SENSOR2") (pin "7") (pinfunction "GND_7") (pintype "power_in"))
      (node (ref "SJ1") (pin "1") (pinfunction "1_1") (pintype "passive"))
      (node (ref "TP4") (pin "TP") (pinfunction "TP_TP") (pintype "input"))
      (node (ref "TP5") (pin "TP") (pinfunction "TP_TP") (pintype "input"))
      (node (ref "U2") (pin "1") (pinfunction "GND_1") (pintype "power_in"))
      (node (ref "U2") (pin "28") (pinfunction "GND_28") (pintype "power_in"))
      (node (ref "U2") (pin "29_1") (pinfunction "GND_29_1") (pintype "power_in"))
      (node (ref "U2") (pin "29_2") (pinfunction "GND_29_2") (pintype "power_in"))
      (node (ref "U2") (pin "29_3") (pinfunction "GND_29_3") (pintype "power_in"))
      (node (ref "U2") (pin "29_4") (pinfunction "GND_29_4") (pintype "power_in"))
      (node (ref "U2") (pin "29_5") (pinfunction "GND_29_5") (pintype "power_in"))
      (node (ref "U2") (pin "29_6") (pinfunction "GND_29_6") (pintype "power_in"))
      (node (ref "U2") (pin "29_7") (pinfunction "GND_29_7") (pintype "power_in"))
      (node (ref "U2") (pin "29_8") (pinfunction "GND_29_8") (pintype "power_in"))
      (node (ref "U2") (pin "29_9") (pinfunction "GND_29_9") (pintype "power_in"))
      (node (ref "U3") (pin "13") (pinfunction "GND_13") (pintype "power_in"))
      (node (ref "U4") (pin "1") (pinfunction "CTG_1") (pintype "power_in"))
      (node (ref "U4") (pin "4") (pinfunction "GND_4") (pintype "power_in"))
      (node (ref "U4") (pin "6") (pinfunction "QSTRT_6") (pintype "input"))
      (node (ref "U4") (pin "9") (pinfunction "EP_9") (pintype "power_in"))
      (node (ref "U5") (pin "4") (pinfunction "GND_4") (pintype "power_in"))
      (node (ref "U5") (pin "9") (pinfunction "EXP_9") (pintype "passive"))
    )
    (net (code "14") (name "GPIO8") (class "Default")
      (node (ref "R1") (pin "2") (pinfunction "2_2") (pintype "passive"))
      (node (ref "U2") (pin "10") (pinfunction "IO8_10") (pintype "bidirectional"))
    )
    (net (code "15") (name "I2C_PW") (class "Default")
      (node (ref "C1") (pin "1") (pinfunction "1_1") (pintype "passive"))
      (node (ref "C2") (pin "1") (pinfunction "1_1") (pintype "passive"))
      (node (ref "R2_PINH") (pin "2") (pinfunction "2_2") (pintype "passive"))
      (node (ref "RI_PINH") (pin "2") (pinfunction "2_2") (pintype "passive"))
      (node (ref "U2") (pin "17") (pinfunction "IO19_17") (pintype "bidirectional"))
    )
    (net (code "16") (name "INT_RTC") (class "Default")
      (node (ref "R1_PINH1") (pin "1") (pinfunction "1_1") (pintype "passive"))
      (node (ref "TP15") (pin "TP") (pinfunction "TP_TP") (pintype "input"))
      (node (ref "U2") (pin "8") (pinfunction "IO0_8") (pintype "bidirectional"))
      (node (ref "U3") (pin "3") (pinfunction "SQW/~{INT}_3") (pintype "output"))
    )
    (net (code "17") (name "IO{slash}BOOT") (class "Default")
      (node (ref "BOOT_BUTTON") (pin "3") (pinfunction "3_3") (pintype "passive"))
      (node (ref "BOOT_BUTTON") (pin "4") (pinfunction "4_4") (pintype "passive"))
      (node (ref "C6") (pin "1") (pinfunction "1_1") (pintype "passive"))
      (node (ref "R_BOOT") (pin "2") (pinfunction "2_2") (pintype "passive"))
      (node (ref "U2") (pin "15") (pinfunction "IO9_15") (pintype "bidirectional"))
    )
    (net (code "18") (name "IO{slash}CHANGE") (class "Default")
      (node (ref "C10") (pin "1") (pinfunction "1_1") (pintype "passive"))
      (node (ref "CHANGE_BUTTON") (pin "3") (pinfunction "3_3") (pintype "passive"))
      (node (ref "CHANGE_BUTTON") (pin "4") (pinfunction "4_4") (pintype "passive"))
      (node (ref "R_CHANGE") (pin "2") (pinfunction "2_2") (pintype "passive"))
      (node (ref "U2") (pin "23") (pinfunction "IO15_23") (pintype "bidirectional"))
    )
    (net (code "19") (name "MISO") (class "Default")
      (node (ref "D12") (pin "1") (pinfunction "1_1") (pintype "passive"))
      (node (ref "J4") (pin "P7") (pinfunction "DAT0_P7") (pintype "bidirectional"))
      (node (ref "R8") (pin "1") (pinfunction "1_1") (pintype "passive"))
      (node (ref "TP6") (pin "TP") (pinfunction "TP_TP") (pintype "input"))
      (node (ref "U2") (pin "27") (pinfunction "IO2_27") (pintype "bidirectional"))
      (node (ref "U5") (pin "2") (pinfunction "DO(IO1)_2") (pintype "bidirectional"))
    )
    (net (code "20") (name "MOSI") (class "Default")
      (node (ref "D11") (pin "1") (pinfunction "1_1") (pintype "passive"))
      (node (ref "J1") (pin "14") (pinfunction "14_14") (pintype "bidirectional"))
      (node (ref "J4") (pin "P3") (pinfunction "CMD_P3") (pintype "bidirectional"))
      (node (ref "R7") (pin "1") (pinfunction "1_1") (pintype "passive"))
      (node (ref "TP7") (pin "TP") (pinfunction "TP_TP") (pintype "input"))
      (node (ref "U2") (pin "7") (pinfunction "IO7_7") (pintype "bidirectional"))
      (node (ref "U5") (pin "5") (pinfunction "DI(IO0)_5") (pintype "bidirectional"))
    )
    (net (code "21") (name "Net-(C4_USB-Pad1)") (class "Default")
      (node (ref "C4_USB") (pin "1") (pinfunction "1_1") (pintype "passive"))
      (node (ref "C5_USB") (pin "1") (pinfunction "1_1") (pintype "passive"))
    )
    (net (code "22") (name "Net-(CHG_LED-PadC)") (class "Default")
      (node (ref "CHG_LED") (pin "C") (pinfunction "C_C") (pintype "passive"))
      (node (ref "R1_BAT") (pin "2") (pinfunction "2_2") (pintype "passive"))
    )
    (net (code "23") (name "Net-(D2-ANODE)") (class "Default")
      (node (ref "D2") (pin "2") (pinfunction "ANODE_2") (pintype "bidirectional"))
      (node (ref "Q1") (pin "1") (pinfunction "G_1") (pintype "bidirectional"))
      (node (ref "R1_PWRUSB") (pin "2") (pinfunction "2_2") (pintype "passive"))
    )
    (net (code "24") (name "Net-(D2-CATHODE)") (class "Default")
      (node (ref "C1_BAT1") (pin "1") (pinfunction "1_1") (pintype "passive"))
      (node (ref "D2") (pin "1") (pinfunction "CATHODE_1") (pintype "bidirectional"))
      (node (ref "IC4") (pin "1") (pinfunction "VIN_1") (pintype "bidirectional"))
      (node (ref "IC4") (pin "3") (pinfunction "CE_3") (pintype "bidirectional"))
      (node (ref "Q1") (pin "2") (pinfunction "S_2") (pintype "bidirectional"))
    )
    (net (code "25") (name "Net-(D3-A)") (class "Default")
      (node (ref "C4") (pin "1") (pinfunction "1_1") (pintype "passive"))
      (node (ref "D3") (pin "2") (pinfunction "A_2") (pintype "bidirectional"))
      (node (ref "D4") (pin "1") (pinfunction "K_1") (pintype "bidirectional"))
    )
    (net (code "26") (name "Net-(D5-A)") (class "Default")
      (node (ref "C4") (pin "2") (pinfunction "2_2") (pintype "passive"))
      (node (ref "D5") (pin "2") (pinfunction "A_2") (pintype "bidirectional"))
      (node (ref "L1") (pin "1") (pinfunction "1_1") (pintype "passive"))
    )
    (net (code "27") (name "Net-(D7-CATHODE)") (class "Default")
      (node (ref "D7") (pin "1") (pinfunction "CATHODE_1") (pintype "bidirectional"))
      (node (ref "R_CAPACITOR") (pin "1") (pinfunction "1_1") (pintype "passive"))
    )
    (net (code "28") (name "Net-(EPD_C1-Pad1)") (class "Default")
      (node (ref "EPD_C1") (pin "1") (pinfunction "1_1") (pintype "passive"))
      (node (ref "J1") (pin "4") (pinfunction "4_4") (pintype "bidirectional"))
    )
    (net (code "29") (name "Net-(EPD_C2-Pad1)") (class "Default")
      (node (ref "EPD_C2") (pin "1") (pinfunction "1_1") (pintype "passive"))
      (node (ref "J1") (pin "5") (pinfunction "5_5") (pintype "bidirectional"))
    )
    (net (code "30") (name "Net-(EPD_C6-Pad1)") (class "Default")
      (node (ref "EPD_C6") (pin "1") (pinfunction "1_1") (pintype "passive"))
      (node (ref "J1") (pin "18") (pinfunction "18_18") (pintype "bidirectional"))
    )
    (net (code "31") (name "Net-(EPD_C7-Pad1)") (class "Default")
      (node (ref "EPD_C7") (pin "1") (pinfunction "1_1") (pintype "passive"))
      (node (ref "J1") (pin "19") (pinfunction "19_19") (pintype "bidirectional"))
    )
    (net (code "32") (name "Net-(EPD_C8-Pad1)") (class "Default")
      (node (ref "EPD_C8") (pin "1") (pinfunction "1_1") (pintype "passive"))
      (node (ref "J1") (pin "20") (pinfunction "20_20") (pintype "bidirectional"))
    )
    (net (code "33") (name "Net-(EPD_C10-Pad1)") (class "Default")
      (node (ref "EPD_C10") (pin "1") (pinfunction "1_1") (pintype "passive"))
      (node (ref "J1") (pin "22") (pinfunction "22_22") (pintype "bidirectional"))
    )
    (net (code "34") (name "Net-(EPD_C12-Pad1)") (class "Default")
      (node (ref "EPD_C12") (pin "1") (pinfunction "1_1") (pintype "passive"))
      (node (ref "J1") (pin "24") (pinfunction "24_24") (pintype "bidirectional"))
    )
    (net (code "35") (name "Net-(IC1-VOUT)") (class "Default")
      (node (ref "C_DELAY") (pin "1") (pinfunction "1_1") (pintype "passive"))
      (node (ref "IC1") (pin "5") (pinfunction "VOUT_5") (pintype "bidirectional"))
    )
    (net (code "36") (name "Net-(J2-PadA5)") (class "Default")
      (node (ref "J2") (pin "A5") (pinfunction "A5_A5") (pintype "bidirectional"))
      (node (ref "R2-USB1") (pin "2") (pinfunction "2_2") (pintype "passive"))
    )
    (net (code "37") (name "Net-(J2-PadB5)") (class "Default")
      (node (ref "J2") (pin "B5") (pinfunction "B5_B5") (pintype "bidirectional"))
      (node (ref "R2-USB") (pin "1") (pinfunction "1_1") (pintype "passive"))
    )
    (net (code "38") (name "Net-(MCP73831-PROG)") (class "Default")
      (node (ref "MCP73831") (pin "5") (pinfunction "PROG_5") (pintype "input"))
      (node (ref "R2_BAT") (pin "2") (pinfunction "2_2") (pintype "passive"))
    )
    (net (code "39") (name "Net-(MCP73831-STAT)") (class "Default")
      (node (ref "MCP73831") (pin "1") (pinfunction "STAT_1") (pintype "output"))
      (node (ref "R1_BAT") (pin "1") (pinfunction "1_1") (pintype "passive"))
    )
    (net (code "40") (name "Net-(MCP73831-VBAT)") (class "Default")
      (node (ref "C2_BAT") (pin "1") (pinfunction "1_1") (pintype "passive"))
      (node (ref "MCP73831") (pin "3") (pinfunction "VBAT_3") (pintype "power_in"))
    )
    (net (code "41") (name "Net-(MCP73831-VIN)") (class "Default")
      (node (ref "C1_BAT") (pin "1") (pinfunction "1_1") (pintype "passive"))
      (node (ref "CHG_LED") (pin "A") (pinfunction "A_A") (pintype "passive"))
      (node (ref "MCP73831") (pin "4") (pinfunction "VIN_4") (pintype "power_in"))
    )
    (net (code "42") (name "Net-(SENSOR2-CSB)") (class "Default")
      (node (ref "SENSOR2") (pin "2") (pinfunction "CSB_2") (pintype "input"))
      (node (ref "SENSOR2") (pin "6") (pinfunction "VDDIO_6") (pintype "power_in"))
      (node (ref "SENSOR2") (pin "8") (pinfunction "VDD_8") (pintype "power_in"))
    )
    (net (code "43") (name "PREVGH") (class "Default")
      (node (ref "D5") (pin "1") (pinfunction "K_1") (pintype "bidirectional"))
      (node (ref "EPD_C9") (pin "1") (pinfunction "1_1") (pintype "passive"))
      (node (ref "J1") (pin "21") (pinfunction "21_21") (pintype "bidirectional"))
    )
    (net (code "44") (name "PREVGL") (class "Default")
      (node (ref "D4") (pin "2") (pinfunction "A_2") (pintype "bidirectional"))
      (node (ref "EPD_C11") (pin "1") (pinfunction "1_1") (pintype "passive"))
      (node (ref "J1") (pin "23") (pinfunction "23_23") (pintype "bidirectional"))
    )
    (net (code "45") (name "RESE") (class "Default")
      (node (ref "J1") (pin "3") (pinfunction "3_3") (pintype "bidirectional"))
      (node (ref "Q3") (pin "2") (pinfunction "S_2") (pintype "bidirectional"))
      (node (ref "R3") (pin "1") (pinfunction "1_1") (pintype "passive"))
    )
    (net (code "46") (name "RESE'") (class "Default")
      (node (ref "SJ1") (pin "2") (pinfunction "2_2") (pintype "passive"))
    )
    (net (code "47") (name "RESET") (class "Default")
      (node (ref "C5") (pin "1") (pinfunction "1_1") (pintype "passive"))
      (node (ref "IC1") (pin "1") (pinfunction "VIN_1") (pintype "bidirectional"))
      (node (ref "RESET_BUTTON1") (pin "3") (pinfunction "3_3") (pintype "passive"))
      (node (ref "RESET_BUTTON1") (pin "4") (pinfunction "4_4") (pintype "passive"))
      (node (ref "R_RESET") (pin "2") (pinfunction "2_2") (pintype "passive"))
      (node (ref "U2") (pin "3") (pinfunction "EN_3") (pintype "input"))
    )
    (net (code "48") (name "RTC_RST") (class "Default")
      (node (ref "U2") (pin "16") (pinfunction "IO18_16") (pintype "bidirectional"))
      (node (ref "U3") (pin "4") (pinfunction "~{RST}_4") (pintype "input"))
    )
    (net (code "49") (name "RX") (class "Default")
      (node (ref "TP2") (pin "TP") (pinfunction "TP_TP") (pintype "input"))
      (node (ref "U2") (pin "24") (pinfunction "RXD0/GPIO17_24") (pintype "bidirectional"))
    )
    (net (code "50") (name "SCK") (class "Default")
      (node (ref "D10") (pin "1") (pinfunction "1_1") (pintype "passive"))
      (node (ref "J1") (pin "13") (pinfunction "13_13") (pintype "bidirectional"))
      (node (ref "J4") (pin "P5") (pinfunction "CLK_P5") (pintype "bidirectional"))
      (node (ref "R6") (pin "1") (pinfunction "1_1") (pintype "passive"))
      (node (ref "TP8") (pin "TP") (pinfunction "TP_TP") (pintype "input"))
      (node (ref "U2") (pin "6") (pinfunction "IO6_6") (pintype "bidirectional"))
      (node (ref "U5") (pin "6") (pinfunction "CLK_6") (pintype "input"))
    )
    (net (code "51") (name "SCL") (class "Default")
      (node (ref "R2_PINH") (pin "1") (pinfunction "1_1") (pintype "passive"))
      (node (ref "SENSOR2") (pin "4") (pinfunction "SCK_4") (pintype "input"))
      (node (ref "U2") (pin "20") (pinfunction "IO22_20") (pintype "bidirectional"))
      (node (ref "U4") (pin "7") (pinfunction "SCL_7") (pintype "input"))
    )
    (net (code "52") (name "SDA") (class "Default")
      (node (ref "RI_PINH") (pin "1") (pinfunction "1_1") (pintype "passive"))
      (node (ref "SENSOR2") (pin "3") (pinfunction "SDI_3") (pintype "bidirectional"))
      (node (ref "U2") (pin "19") (pinfunction "IO21_19") (pintype "bidirectional"))
      (node (ref "U4") (pin "8") (pinfunction "SDA_8") (pintype "bidirectional"))
    )
    (net (code "53") (name "SRC") (class "Default")
      (node (ref "Q3") (pin "3") (pinfunction "D_3") (pintype "bidirectional"))
    )
    (net (code "54") (name "SS_SD") (class "Default")
      (node (ref "D8") (pin "1") (pinfunction "1_1") (pintype "passive"))
      (node (ref "J4") (pin "P2") (pinfunction "CD/DAT3_P2") (pintype "bidirectional"))
      (node (ref "R10") (pin "1") (pinfunction "1_1") (pintype "passive"))
      (node (ref "U2") (pin "4") (pinfunction "IO4_4") (pintype "bidirectional"))
    )
    (net (code "55") (name "TX") (class "Default")
      (node (ref "TP1") (pin "TP") (pinfunction "TP_TP") (pintype "input"))
      (node (ref "U2") (pin "25") (pinfunction "TXD0/GPIO16_25") (pintype "bidirectional"))
    )
    (net (code "56") (name "USB_D+") (class "Default")
      (node (ref "D1") (pin "1") (pinfunction "I/O1_1_1") (pintype "bidirectional"))
      (node (ref "U2") (pin "14") (pinfunction "IO13_14") (pintype "bidirectional"))
    )
    (net (code "57") (name "USB_D-") (class "Default")
      (node (ref "D1") (pin "3") (pinfunction "I/O2_1_3") (pintype "bidirectional"))
      (node (ref "U2") (pin "13") (pinfunction "IO12_13") (pintype "bidirectional"))
    )
    (net (code "58") (name "VBAT") (class "Default")
      (node (ref "Q1") (pin "3") (pinfunction "D_3") (pintype "bidirectional"))
      (node (ref "TP3") (pin "TP") (pinfunction "TP_TP") (pintype "input"))
      (node (ref "U4") (pin "2") (pinfunction "CELL_2") (pintype "power_in"))
      (node (ref "U4") (pin "3") (pinfunction "VDD_3") (pintype "power_in"))
    )
    (net (code "59") (name "VBUS") (class "Default")
      (node (ref "PFMF.050.1") (pin "2") (pinfunction "2_2") (pintype "passive"))
      (node (ref "TP14") (pin "TP") (pinfunction "TP_TP") (pintype "input"))
    )
    (net (code "60") (name "VRTC") (class "Default")
      (node (ref "C10_SUPERCAP") (pin "2") (pinfunction "2_2") (pintype "passive"))
      (node (ref "C8") (pin "1") (pinfunction "1_1") (pintype "passive"))
      (node (ref "R_CAPACITOR") (pin "2") (pinfunction "2_2") (pintype "passive"))
    )
    (net (code "61") (name "VUSB") (class "Default")
      (node (ref "J2") (pin "A4") (pinfunction "A4_A4") (pintype "bidirectional"))
      (node (ref "PFMF.050.1") (pin "1") (pinfunction "1_1") (pintype "passive"))
    )
    (net (code "62") (name "unconnected-(D1-I{slash}O1_2-Pad6)") (class "Default")
      (node (ref "D1") (pin "6") (pinfunction "I/O1_2_6") (pintype "bidirectional"))
    )
    (net (code "63") (name "unconnected-(D1-I{slash}O2_2-Pad4)") (class "Default")
      (node (ref "D1") (pin "4") (pinfunction "I/O2_2_4") (pintype "bidirectional"))
    )
    (net (code "64") (name "unconnected-(D1-VBUS-Pad5)") (class "Default")
      (node (ref "D1") (pin "5") (pinfunction "VBUS_5") (pintype "bidirectional"))
    )
    (net (code "65") (name "unconnected-(IC1-NC-Pad4)") (class "Default")
      (node (ref "IC1") (pin "4") (pinfunction "NC_4") (pintype "no_connect"))
    )
    (net (code "66") (name "unconnected-(IC4-NC-Pad4)") (class "Default")
      (node (ref "IC4") (pin "4") (pinfunction "NC_4") (pintype "no_connect"))
    )
    (net (code "67") (name "unconnected-(J1-Pad1)") (class "Default")
      (node (ref "J1") (pin "1") (pinfunction "1_1") (pintype "bidirectional"))
    )
    (net (code "68") (name "unconnected-(J1-Pad6)") (class "Default")
      (node (ref "J1") (pin "6") (pinfunction "6_6") (pintype "bidirectional"))
    )
    (net (code "69") (name "unconnected-(J1-Pad7)") (class "Default")
      (node (ref "J1") (pin "7") (pinfunction "7_7") (pintype "bidirectional"))
    )
    (net (code "70") (name "unconnected-(J2-PadA8)") (class "Default")
      (node (ref "J2") (pin "A8") (pinfunction "A8_A8") (pintype "bidirectional"))
    )
    (net (code "71") (name "unconnected-(J2-PadA9)") (class "Default")
      (node (ref "J2") (pin "A9") (pinfunction "A9_A9") (pintype "bidirectional"))
    )
    (net (code "72") (name "unconnected-(J2-PadB4)") (class "Default")
      (node (ref "J2") (pin "B4") (pinfunction "B4_B4") (pintype "bidirectional"))
    )
    (net (code "73") (name "unconnected-(J2-PadB6)") (class "Default")
      (node (ref "J2") (pin "B6") (pinfunction "B6_B6") (pintype "bidirectional"))
    )
    (net (code "74") (name "unconnected-(J2-PadB7)") (class "Default")
      (node (ref "J2") (pin "B7") (pinfunction "B7_B7") (pintype "bidirectional"))
    )
    (net (code "75") (name "unconnected-(J2-PadB8)") (class "Default")
      (node (ref "J2") (pin "B8") (pinfunction "B8_B8") (pintype "bidirectional"))
    )
    (net (code "76") (name "unconnected-(J2-PadB9)") (class "Default")
      (node (ref "J2") (pin "B9") (pinfunction "B9_B9") (pintype "bidirectional"))
    )
    (net (code "77") (name "unconnected-(J3-Pad3)") (class "Default")
      (node (ref "J3") (pin "3") (pinfunction "3_3") (pintype "passive"))
    )
    (net (code "78") (name "unconnected-(J3-Pad4)") (class "Default")
      (node (ref "J3") (pin "4") (pinfunction "4_4") (pintype "passive"))
    )
    (net (code "79") (name "unconnected-(J4-DAT1-PadP8)") (class "Default")
      (node (ref "J4") (pin "P8") (pinfunction "DAT1_P8") (pintype "bidirectional"))
    )
    (net (code "80") (name "unconnected-(J4-DAT2-PadP1)") (class "Default")
      (node (ref "J4") (pin "P1") (pinfunction "DAT2_P1") (pintype "bidirectional"))
    )
    (net (code "81") (name "unconnected-(J4-DETECTION_1-PadS1)") (class "Default")
      (node (ref "J4") (pin "S1") (pinfunction "DETECTION_1_S1") (pintype "bidirectional"))
    )
    (net (code "82") (name "unconnected-(J4-DETECTION_2-PadS2)") (class "Default")
      (node (ref "J4") (pin "S2") (pinfunction "DETECTION_2_S2") (pintype "bidirectional"))
    )
    (net (code "83") (name "unconnected-(R2-Pad2)") (class "Default")
      (node (ref "R2") (pin "2") (pinfunction "2_2") (pintype "passive"))
    )
    (net (code "84") (name "unconnected-(R3-Pad2)") (class "Default")
      (node (ref "R3") (pin "2") (pinfunction "2_2") (pintype "passive"))
    )
    (net (code "85") (name "unconnected-(U2-NC-Pad22)") (class "Default")
      (node (ref "U2") (pin "22") (pinfunction "NC_22") (pintype "no_connect"))
    )
    (net (code "86") (name "unconnected-(U3-SCL-Pad16)") (class "Default")
      (node (ref "U3") (pin "16") (pinfunction "SCL_16") (pintype "input"))
    )
    (net (code "87") (name "unconnected-(U3-SDA-Pad15)") (class "Default")
      (node (ref "U3") (pin "15") (pinfunction "SDA_15") (pintype "bidirectional"))
    )
    (net (code "88") (name "unconnected-(U3-VBAT-Pad14)") (class "Default")
      (node (ref "U3") (pin "14") (pinfunction "VBAT_14") (pintype "power_in"))
    )
    (net (code "89") (name "unconnected-(U4-~{ALERT}-Pad5)") (class "Default")
      (node (ref "U4") (pin "5") (pinfunction "~{ALERT}_5") (pintype "output"))
    )
  )
)
